# Power_Supply.net
KiCad netlist of a schematic drawn in Altium Designer
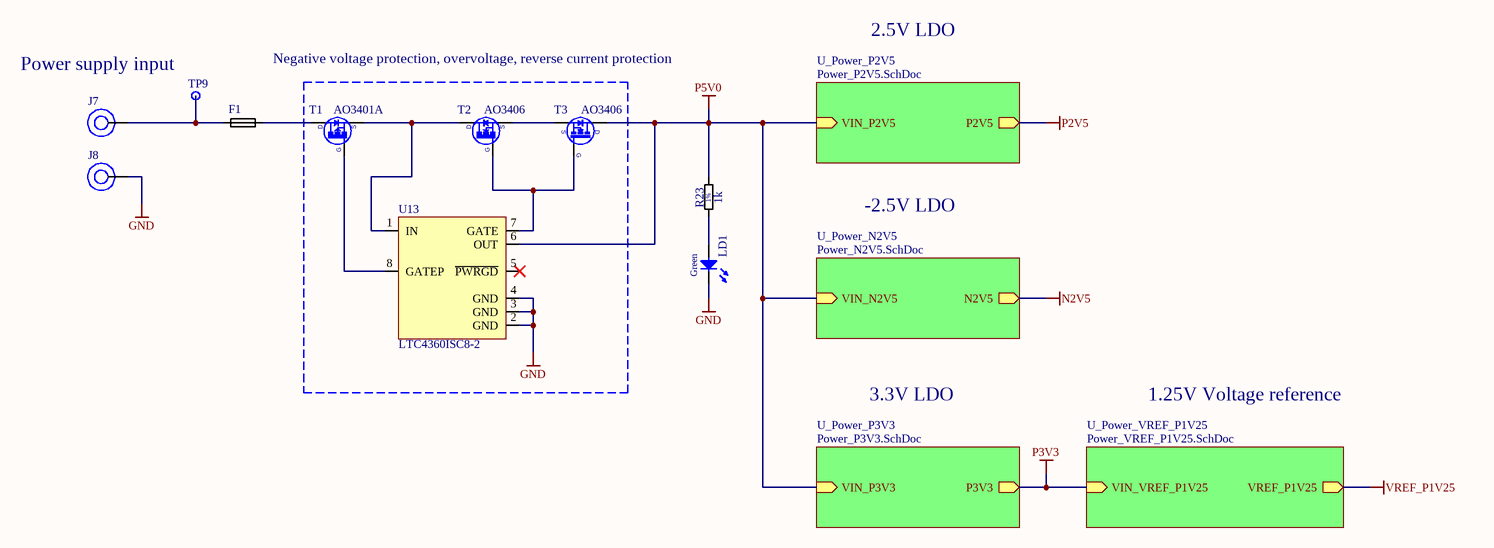
[diagram p0: Power_Supply.SchDoc]

(export (version "E")
  (design (tool "Eeschema 10.0.6"))
  (components
    (comp (ref "F1")
      (value "C1Q 1.5")
      (footprint "FUSE1206")
      (description "Fuse; Very Fast Acting; 1.5A; 125VAC, 63VDC; SMD;")
      (libsource (lib "Fuses") (part "Fuse"))
    )
    (comp (ref "J7")
      (value "571-0500")
      (footprint "5710500-Deltron")
      (description "4mm Jack 90deg PCB Mounted Insulated Socket Red")
      (libsource (lib "Connectors") (part "Jack banana x1"))
    )
    (comp (ref "J8")
      (value "571-0100")
      (footprint "5710100-Deltron")
      (description "4mm Jack 90deg PCB Mounted Insulated Socket Black")
      (libsource (lib "Connectors") (part "Jack banana x1"))
    )
    (comp (ref "LD1")
      (value "Green")
      (footprint "LED_0603X60N")
      (description "SMD mono-color Chip LED, Green, 0603")
      (fields (field (name "MANUFACTURER PART NUMBER") "HSME-C191"))
      (libsource (lib "ICs_and_Semiconductors") (part "LED 1C 2A"))
    )
    (comp (ref "R23")
      (value "1k")
      (footprint "RESC0603X60N")
      (description "General Purpose Thick Film Chip Resistor")
      (fields (field (name "MANUFACTURER PART NUMBER") "CQ03SAF1001T5E") (field (name "TOLERANCE") "1%"))
      (libsource (lib "Resistors") (part "Resistor - 1%"))
    )
    (comp (ref "T1")
      (value "AO3401A")
      (footprint "SOT23-3")
      (description "30V P-Channel MOSFET")
      (libsource (lib "ICs_and_Semiconductors") (part "P-MOSFET-D 1G 2S 3D"))
    )
    (comp (ref "T2")
      (value "AO3406")
      (footprint "SOT23-3")
      (description "Transistor: N-MOSFET; unipolar; 30V; 2.9A; 0.9W; SOT23")
      (libsource (lib "ICs_and_Semiconductors") (part "N-MOSFET-D 1G 2S 3D"))
    )
    (comp (ref "T3")
      (value "AO3406")
      (footprint "SOT23-3")
      (description "Transistor: N-MOSFET; unipolar; 30V; 2.9A; 0.9W; SOT23")
      (libsource (lib "") (part "N-MOSFET-D 1G 2S 3D_1"))
    )
    (comp (ref "TP9")
      (value "TestPoint")
      (footprint "TESTPOINT_SMD_C1P27MM")
      (description "1.27mm diameter SMD Test Point Area")
      (libsource (lib "Mechanical_and_PCB_Features") (part "Test Point"))
    )
    (comp (ref "U13")
      (value "LTC4360ISC8-2")
      (footprint "SC70-8")
      (description "Overvoltage Protection Controller, 2.5V to 5.5V Operation, Reverse Voltage Protection")
      (fields (field (name "MANUFACTURER PART NUMBER") "LTC4360ISC8-2#TRMPBF"))
      (libsource (lib "ICs_and_Semiconductors") (part "LTC4360ISC8-2"))
    )
  )
  (nets
    (net (code "1") (name "GND") (class "Default")
      (node (ref "J8") (pin "1") (pinfunction "1_1") (pintype "passive"))
      (node (ref "LD1") (pin "1") (pinfunction "C_1") (pintype "passive"))
      (node (ref "U13") (pin "2") (pinfunction "GND_2") (pintype "passive"))
      (node (ref "U13") (pin "3") (pinfunction "GND_3") (pintype "passive"))
      (node (ref "U13") (pin "4") (pinfunction "GND_4") (pintype "passive"))
    )
    (net (code "3") (name "Net-(F1-Pad1)") (class "Default")
      (node (ref "F1") (pin "1") (pinfunction "1_1") (pintype "passive"))
      (node (ref "J7") (pin "1") (pinfunction "1_1") (pintype "passive"))
      (node (ref "TP9") (pin "1") (pinfunction "1_1") (pintype "passive"))
    )
    (net (code "4") (name "Net-(LD1-A)") (class "Default")
      (node (ref "LD1") (pin "2") (pinfunction "A_2") (pintype "passive"))
      (node (ref "R23") (pin "1") (pinfunction "1_1") (pintype "passive"))
    )
    (net (code "5") (name "Net-(T1-D)") (class "Default")
      (node (ref "F1") (pin "2") (pinfunction "2_2") (pintype "passive"))
      (node (ref "T1") (pin "3") (pinfunction "D_3") (pintype "passive"))
    )
    (net (code "6") (name "Net-(T1-G)") (class "Default")
      (node (ref "T1") (pin "1") (pinfunction "G_1") (pintype "passive"))
      (node (ref "U13") (pin "8") (pinfunction "GATEP_8") (pintype "passive"))
    )
    (net (code "7") (name "Net-(T1-S)") (class "Default")
      (node (ref "T1") (pin "2") (pinfunction "S_2") (pintype "passive"))
      (node (ref "T2") (pin "3") (pinfunction "D_3") (pintype "passive"))
      (node (ref "U13") (pin "1") (pinfunction "IN_1") (pintype "passive"))
    )
    (net (code "8") (name "Net-(T2-G)") (class "Default")
      (node (ref "T2") (pin "1") (pinfunction "G_1") (pintype "passive"))
      (node (ref "T3") (pin "1") (pinfunction "G_1") (pintype "passive"))
      (node (ref "U13") (pin "7") (pinfunction "GATE_7") (pintype "passive"))
    )
    (net (code "9") (name "Net-(T2-S)") (class "Default")
      (node (ref "T2") (pin "2") (pinfunction "S_2") (pintype "passive"))
      (node (ref "T3") (pin "2") (pinfunction "S_2") (pintype "passive"))
    )
    (net (code "12") (name "P5V0") (class "Default")
      (node (ref "R23") (pin "2") (pinfunction "2_2") (pintype "passive"))
      (node (ref "T3") (pin "3") (pinfunction "D_3") (pintype "passive"))
      (node (ref "U13") (pin "6") (pinfunction "OUT_6") (pintype "passive"))
    )
    (net (code "14") (name "unconnected-(U13-~{PWRGD}-Pad5)") (class "Default")
      (node (ref "U13") (pin "5") (pinfunction "~{PWRGD}_5") (pintype "passive+no_connect"))
    )
  )
)
